# homeboard8.net
KiCad netlist of a schematic drawn in EAGLE
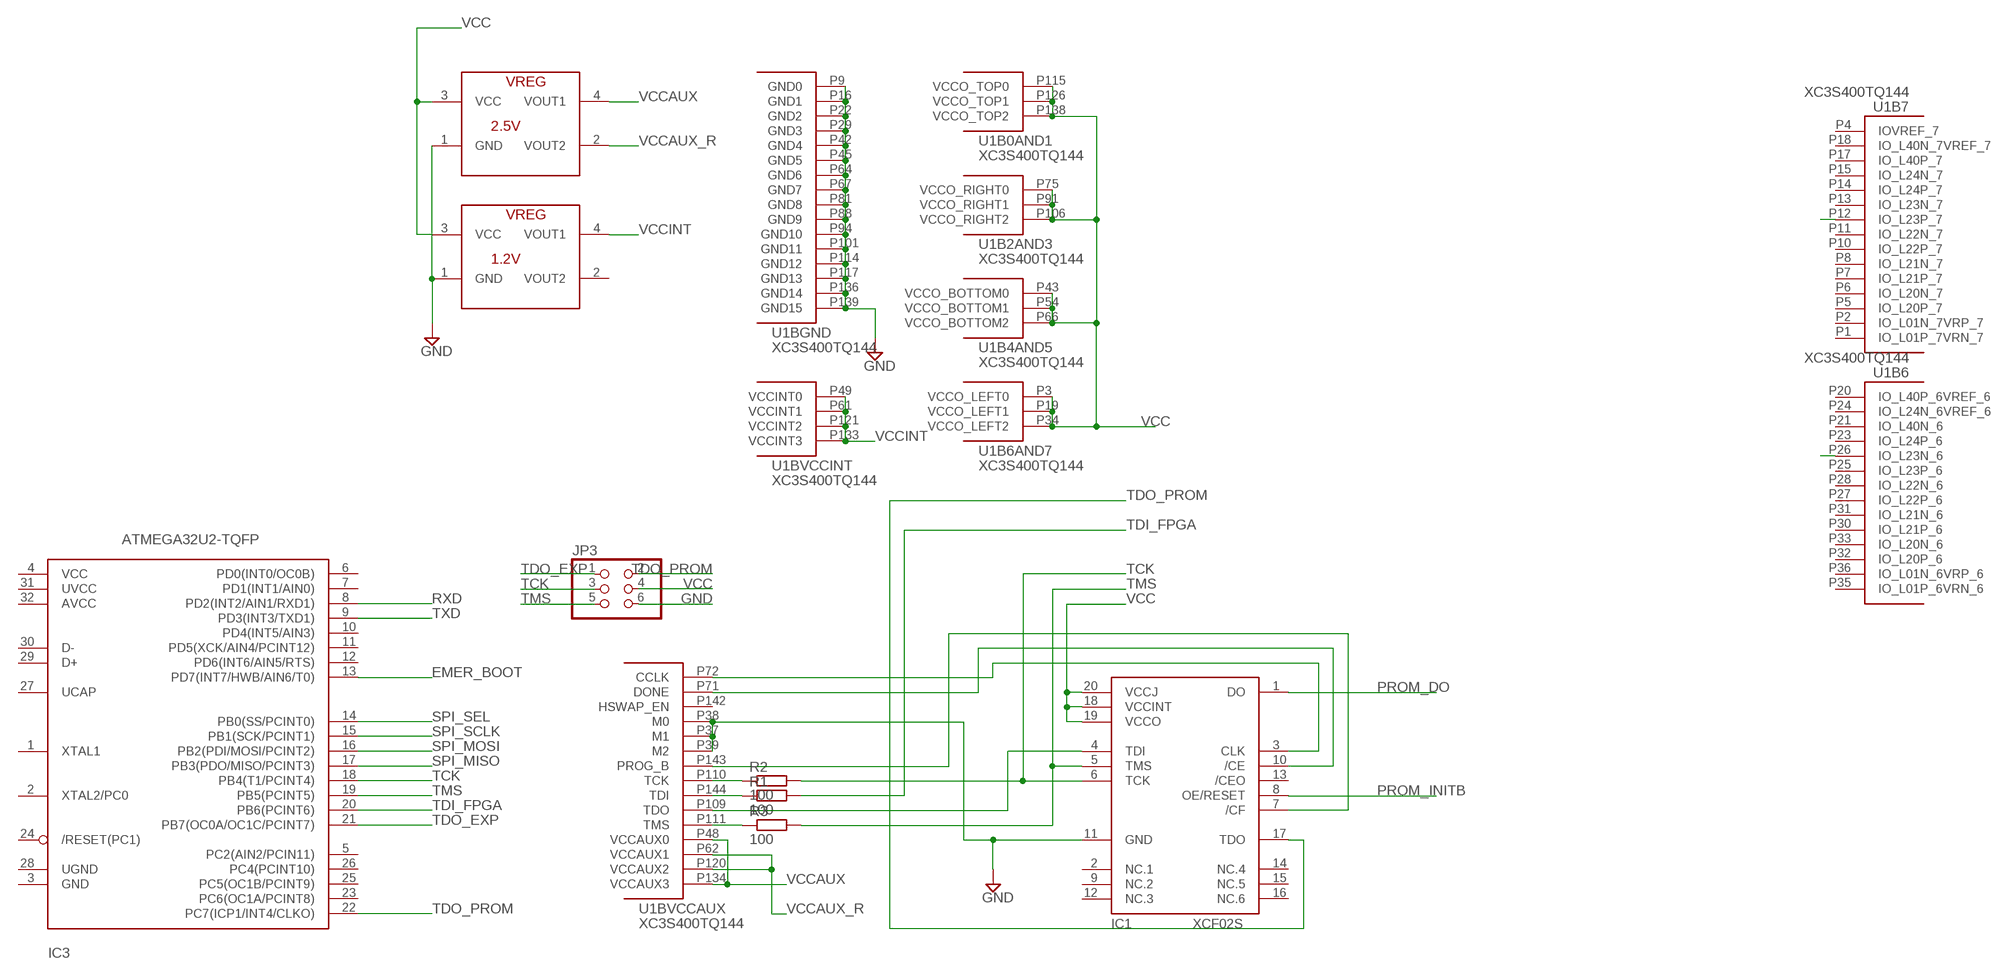
[diagram p0: schematic, sheet 1, part 1 of 3]
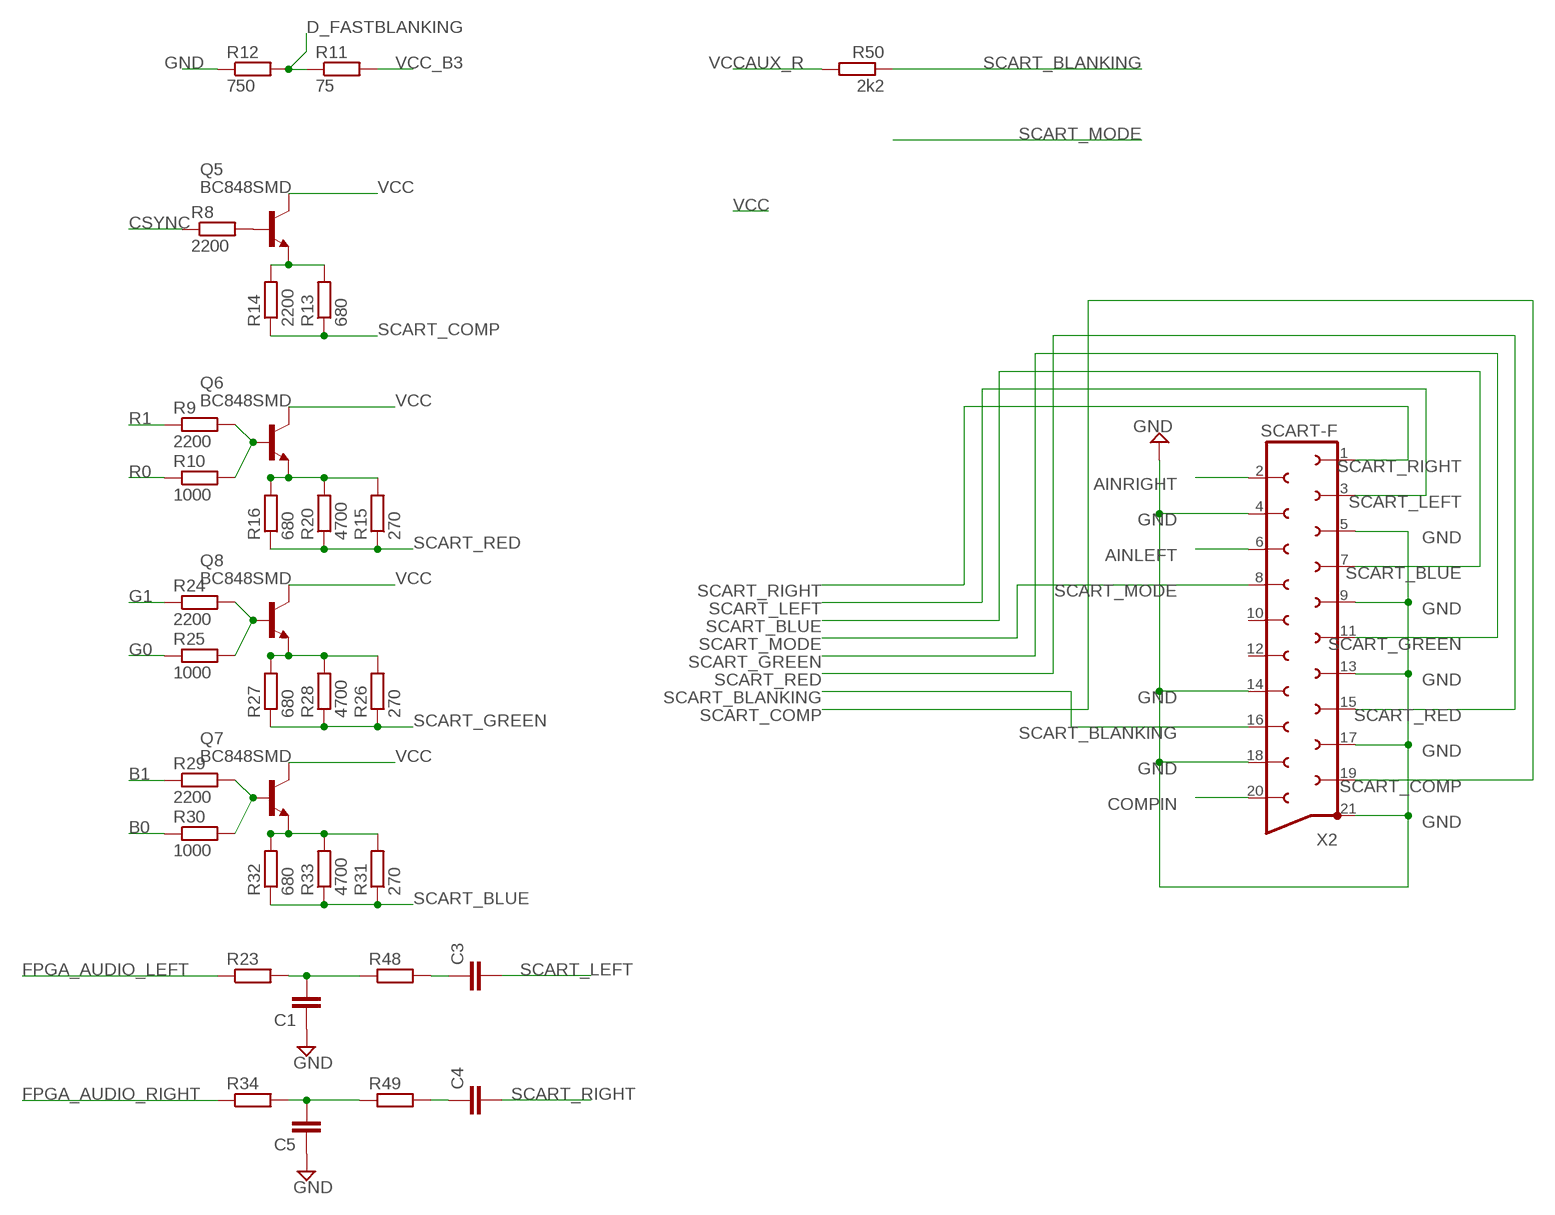
[diagram p1: schematic, sheet 1, part 2 of 3]
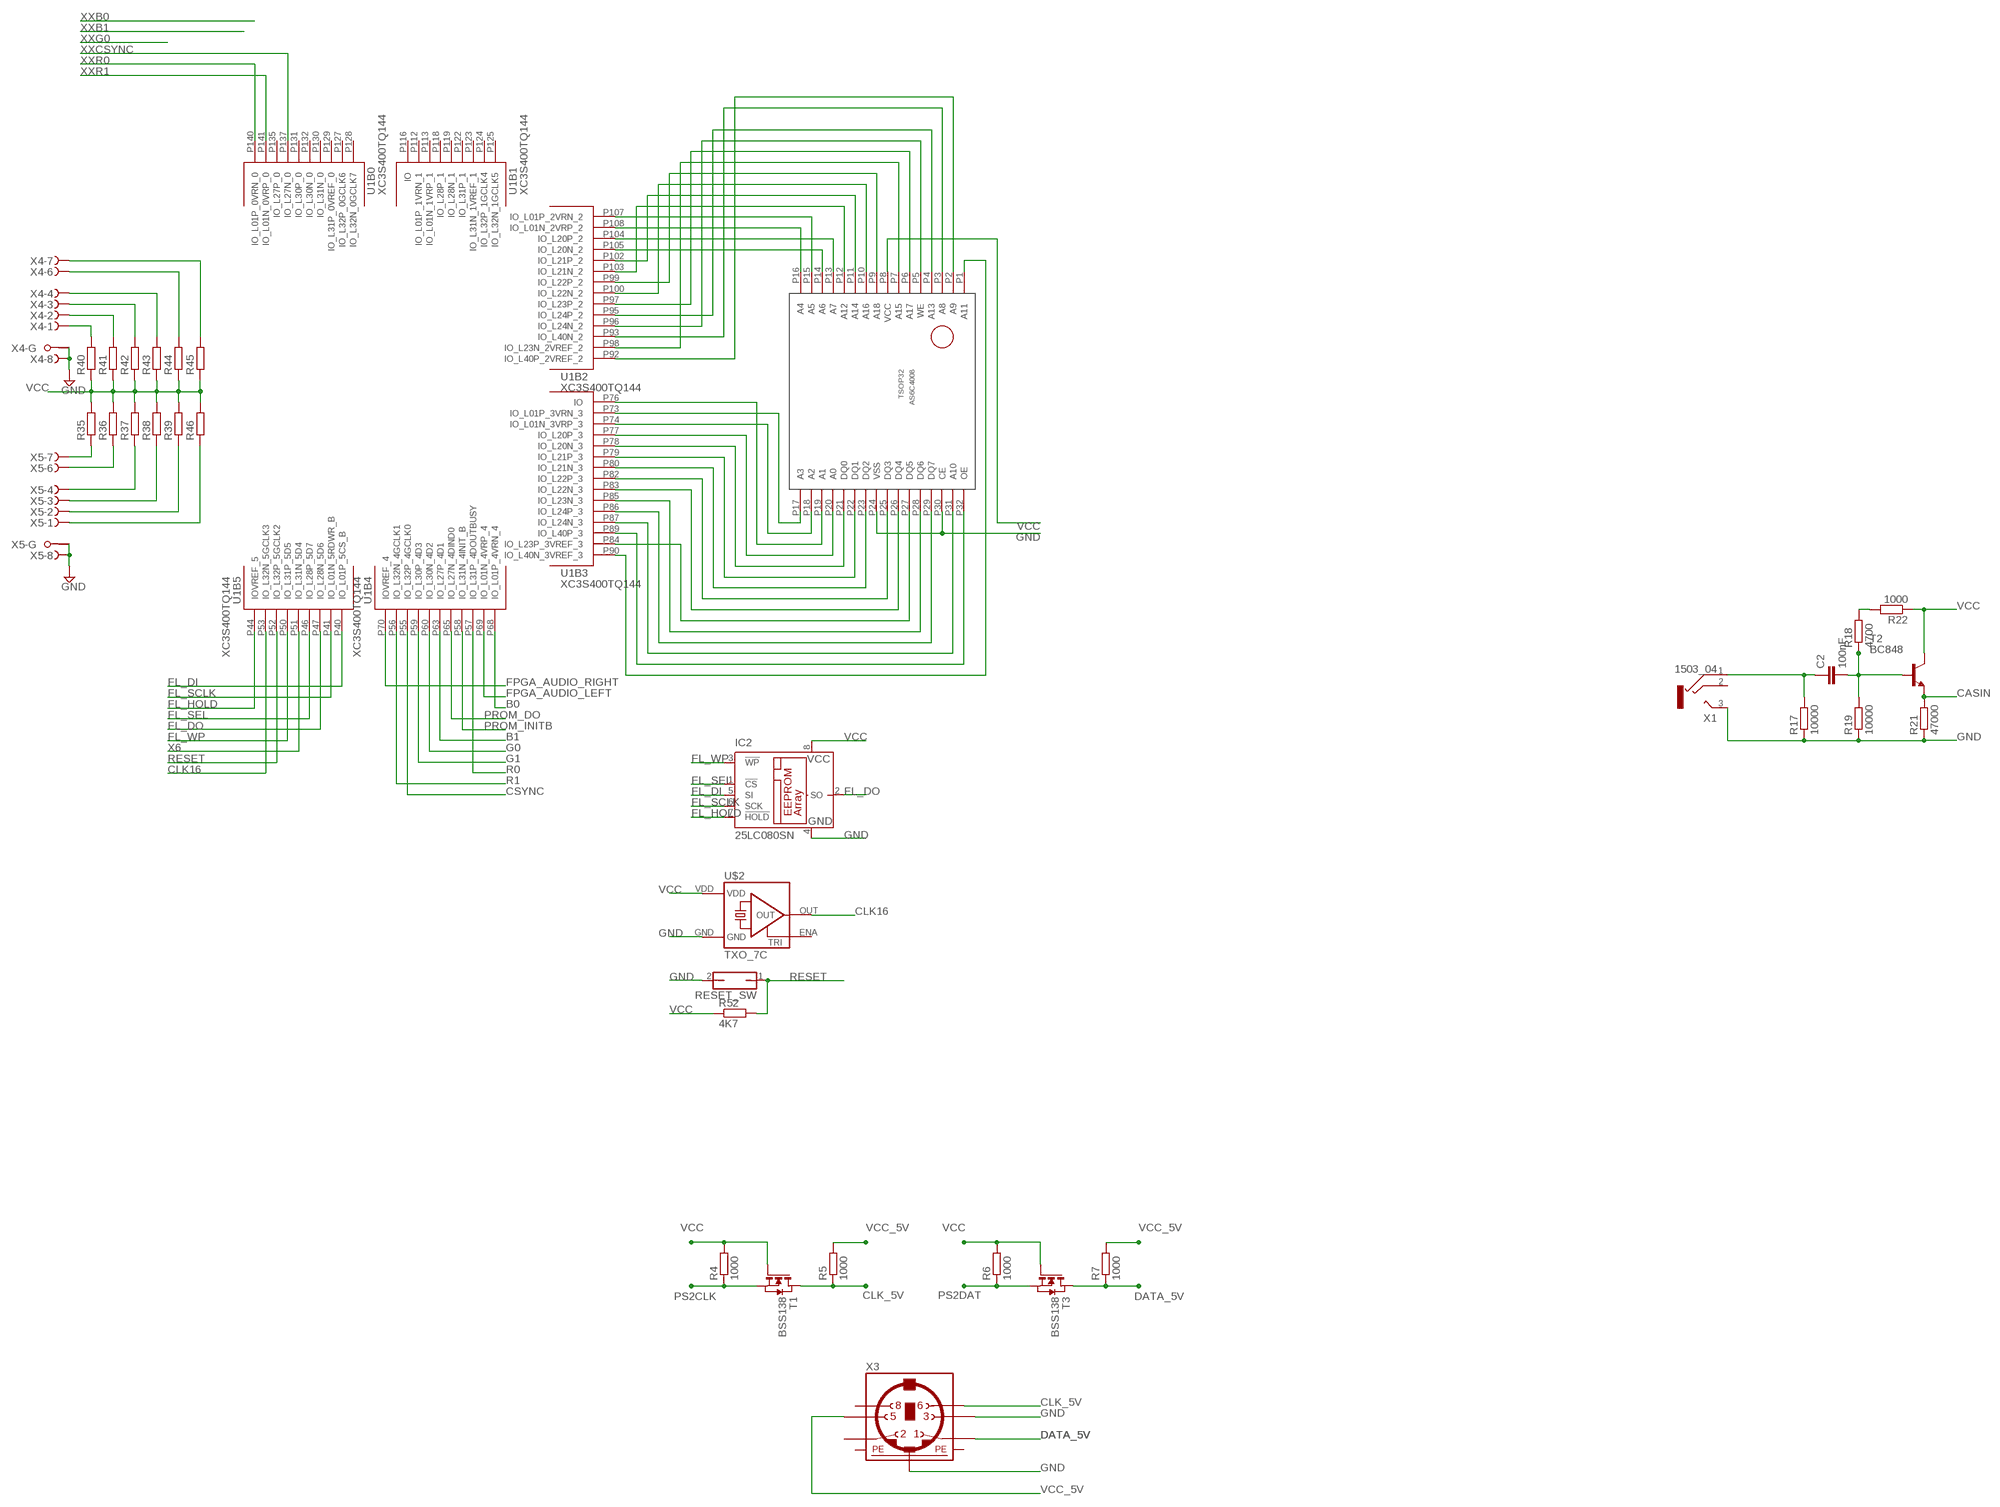
[diagram p2: schematic, sheet 1, part 3 of 3]

(export (version "E")
  (design (tool "Eeschema 10.0.6"))
  (components
    (comp (ref "C1")
      (value "C-EUC0603")
      (footprint "eagle-import:C0603")
      (libsource (lib "eagle-import") (part "C-EUC0603"))
    )
    (comp (ref "C2")
      (value "100nF")
      (footprint "eagle-import:C0603")
      (libsource (lib "eagle-import") (part "C-EUC0603"))
    )
    (comp (ref "C3")
      (value "C-EUC0603")
      (footprint "eagle-import:C0603")
      (libsource (lib "eagle-import") (part "C-EUC0603"))
    )
    (comp (ref "C4")
      (value "C-EUC0603")
      (footprint "eagle-import:C0603")
      (libsource (lib "eagle-import") (part "C-EUC0603"))
    )
    (comp (ref "C5")
      (value "C-EUC0603")
      (footprint "eagle-import:C0603")
      (libsource (lib "eagle-import") (part "C-EUC0603"))
    )
    (comp (ref "IC1")
      (value "XCF02S")
      (footprint "eagle-import:VO20")
      (libsource (lib "eagle-import") (part "XCF02S"))
    )
    (comp (ref "IC2")
      (value "25LC080SN")
      (footprint "eagle-import:SO-08")
      (fields (field (name "MF") "MICROCHIP") (field (name "MPN") "25LC080/SN"))
      (libsource (lib "eagle-import") (part "25SNLC080"))
    )
    (comp (ref "IC3")
      (value "ATMEGA32U2-TQFP")
      (footprint "eagle-import:TQFP32-08")
      (libsource (lib "eagle-import") (part "ATMEGA32U2-TQFP"))
    )
    (comp (ref "JP3")
      (value "PINHD-2X3")
      (footprint "eagle-import:2X03")
      (libsource (lib "eagle-import") (part "PINHD-2X3"))
    )
    (comp (ref "Q5")
      (value "BC848SMD")
      (footprint "eagle-import:SOT23")
      (libsource (lib "eagle-import") (part "BC848SMD"))
    )
    (comp (ref "Q6")
      (value "BC848SMD")
      (footprint "eagle-import:SOT23")
      (libsource (lib "eagle-import") (part "BC848SMD"))
    )
    (comp (ref "Q7")
      (value "BC848SMD")
      (footprint "eagle-import:SOT23")
      (libsource (lib "eagle-import") (part "BC848SMD"))
    )
    (comp (ref "Q8")
      (value "BC848SMD")
      (footprint "eagle-import:SOT23")
      (libsource (lib "eagle-import") (part "BC848SMD"))
    )
    (comp (ref "R1")
      (value "100")
      (footprint "eagle-import:R0805")
      (libsource (lib "eagle-import") (part "R-EU_R0805"))
    )
    (comp (ref "R2")
      (value "100")
      (footprint "eagle-import:R0805")
      (libsource (lib "eagle-import") (part "R-EU_R0805"))
    )
    (comp (ref "R3")
      (value "100")
      (footprint "eagle-import:R0805")
      (libsource (lib "eagle-import") (part "R-EU_R0805"))
    )
    (comp (ref "R4")
      (value "1000")
      (footprint "eagle-import:R0805")
      (libsource (lib "eagle-import") (part "R-EU_R0805"))
    )
    (comp (ref "R5")
      (value "1000")
      (footprint "eagle-import:R0805")
      (libsource (lib "eagle-import") (part "R-EU_R0805"))
    )
    (comp (ref "R6")
      (value "1000")
      (footprint "eagle-import:R0805")
      (libsource (lib "eagle-import") (part "R-EU_R0805"))
    )
    (comp (ref "R7")
      (value "1000")
      (footprint "eagle-import:R0805")
      (libsource (lib "eagle-import") (part "R-EU_R0805"))
    )
    (comp (ref "R8")
      (value "2200")
      (footprint "eagle-import:R0805")
      (libsource (lib "eagle-import") (part "R-EU_R0805"))
    )
    (comp (ref "R9")
      (value "2200")
      (footprint "eagle-import:R0805")
      (libsource (lib "eagle-import") (part "R-EU_R0805"))
    )
    (comp (ref "R10")
      (value "1000")
      (footprint "eagle-import:R0805")
      (libsource (lib "eagle-import") (part "R-EU_R0805"))
    )
    (comp (ref "R11")
      (value "75")
      (footprint "eagle-import:R0805")
      (libsource (lib "eagle-import") (part "R-EU_R0805"))
    )
    (comp (ref "R12")
      (value "750")
      (footprint "eagle-import:R0805")
      (libsource (lib "eagle-import") (part "R-EU_R0805"))
    )
    (comp (ref "R13")
      (value "680")
      (footprint "eagle-import:R0805")
      (libsource (lib "eagle-import") (part "R-EU_R0805"))
    )
    (comp (ref "R14")
      (value "2200")
      (footprint "eagle-import:R0805")
      (libsource (lib "eagle-import") (part "R-EU_R0805"))
    )
    (comp (ref "R15")
      (value "270")
      (footprint "eagle-import:R0805")
      (libsource (lib "eagle-import") (part "R-EU_R0805"))
    )
    (comp (ref "R16")
      (value "680")
      (footprint "eagle-import:R0805")
      (libsource (lib "eagle-import") (part "R-EU_R0805"))
    )
    (comp (ref "R17")
      (value "10000")
      (footprint "eagle-import:R0805")
      (libsource (lib "eagle-import") (part "R-EU_R0805"))
    )
    (comp (ref "R18")
      (value "4700")
      (footprint "eagle-import:R0805")
      (libsource (lib "eagle-import") (part "R-EU_R0805"))
    )
    (comp (ref "R19")
      (value "10000")
      (footprint "eagle-import:R0805")
      (libsource (lib "eagle-import") (part "R-EU_R0805"))
    )
    (comp (ref "R20")
      (value "4700")
      (footprint "eagle-import:R0805")
      (libsource (lib "eagle-import") (part "R-EU_R0805"))
    )
    (comp (ref "R21")
      (value "47000")
      (footprint "eagle-import:R0805")
      (libsource (lib "eagle-import") (part "R-EU_R0805"))
    )
    (comp (ref "R22")
      (value "1000")
      (footprint "eagle-import:R0805")
      (libsource (lib "eagle-import") (part "R-EU_R0805"))
    )
    (comp (ref "R23")
      (value "R-EU_M0805")
      (footprint "eagle-import:M0805")
      (libsource (lib "eagle-import") (part "resistor_R-EU_M0805"))
    )
    (comp (ref "R24")
      (value "2200")
      (footprint "eagle-import:R0805")
      (libsource (lib "eagle-import") (part "R-EU_R0805"))
    )
    (comp (ref "R25")
      (value "1000")
      (footprint "eagle-import:R0805")
      (libsource (lib "eagle-import") (part "R-EU_R0805"))
    )
    (comp (ref "R26")
      (value "270")
      (footprint "eagle-import:R0805")
      (libsource (lib "eagle-import") (part "R-EU_R0805"))
    )
    (comp (ref "R27")
      (value "680")
      (footprint "eagle-import:R0805")
      (libsource (lib "eagle-import") (part "R-EU_R0805"))
    )
    (comp (ref "R28")
      (value "4700")
      (footprint "eagle-import:R0805")
      (libsource (lib "eagle-import") (part "R-EU_R0805"))
    )
    (comp (ref "R29")
      (value "2200")
      (footprint "eagle-import:R0805")
      (libsource (lib "eagle-import") (part "R-EU_R0805"))
    )
    (comp (ref "R30")
      (value "1000")
      (footprint "eagle-import:R0805")
      (libsource (lib "eagle-import") (part "R-EU_R0805"))
    )
    (comp (ref "R31")
      (value "270")
      (footprint "eagle-import:R0805")
      (libsource (lib "eagle-import") (part "R-EU_R0805"))
    )
    (comp (ref "R32")
      (value "680")
      (footprint "eagle-import:R0805")
      (libsource (lib "eagle-import") (part "R-EU_R0805"))
    )
    (comp (ref "R33")
      (value "4700")
      (footprint "eagle-import:R0805")
      (libsource (lib "eagle-import") (part "R-EU_R0805"))
    )
    (comp (ref "R34")
      (value "R-EU_M0805")
      (footprint "eagle-import:M0805")
      (libsource (lib "eagle-import") (part "resistor_R-EU_M0805"))
    )
    (comp (ref "R35")
      (value "R-EU_M0805")
      (footprint "eagle-import:M0805")
      (libsource (lib "eagle-import") (part "resistor_R-EU_M0805"))
    )
    (comp (ref "R36")
      (value "R-EU_M0805")
      (footprint "eagle-import:M0805")
      (libsource (lib "eagle-import") (part "resistor_R-EU_M0805"))
    )
    (comp (ref "R37")
      (value "R-EU_M0805")
      (footprint "eagle-import:M0805")
      (libsource (lib "eagle-import") (part "resistor_R-EU_M0805"))
    )
    (comp (ref "R38")
      (value "R-EU_M0805")
      (footprint "eagle-import:M0805")
      (libsource (lib "eagle-import") (part "resistor_R-EU_M0805"))
    )
    (comp (ref "R39")
      (value "R-EU_M0805")
      (footprint "eagle-import:M0805")
      (libsource (lib "eagle-import") (part "resistor_R-EU_M0805"))
    )
    (comp (ref "R40")
      (value "R-EU_M0805")
      (footprint "eagle-import:M0805")
      (libsource (lib "eagle-import") (part "resistor_R-EU_M0805"))
    )
    (comp (ref "R41")
      (value "R-EU_M0805")
      (footprint "eagle-import:M0805")
      (libsource (lib "eagle-import") (part "resistor_R-EU_M0805"))
    )
    (comp (ref "R42")
      (value "R-EU_M0805")
      (footprint "eagle-import:M0805")
      (libsource (lib "eagle-import") (part "resistor_R-EU_M0805"))
    )
    (comp (ref "R43")
      (value "R-EU_M0805")
      (footprint "eagle-import:M0805")
      (libsource (lib "eagle-import") (part "resistor_R-EU_M0805"))
    )
    (comp (ref "R44")
      (value "R-EU_M0805")
      (footprint "eagle-import:M0805")
      (libsource (lib "eagle-import") (part "resistor_R-EU_M0805"))
    )
    (comp (ref "R45")
      (value "R-EU_M0805")
      (footprint "eagle-import:M0805")
      (libsource (lib "eagle-import") (part "resistor_R-EU_M0805"))
    )
    (comp (ref "R46")
      (value "R-EU_M0805")
      (footprint "eagle-import:M0805")
      (libsource (lib "eagle-import") (part "resistor_R-EU_M0805"))
    )
    (comp (ref "R48")
      (value "R-EU_M0805")
      (footprint "eagle-import:M0805")
      (libsource (lib "eagle-import") (part "resistor_R-EU_M0805"))
    )
    (comp (ref "R49")
      (value "R-EU_M0805")
      (footprint "eagle-import:M0805")
      (libsource (lib "eagle-import") (part "resistor_R-EU_M0805"))
    )
    (comp (ref "R50")
      (value "2k2")
      (footprint "eagle-import:M0805")
      (libsource (lib "eagle-import") (part "resistor_R-EU_M0805"))
    )
    (comp (ref "R52")
      (value "4K7")
      (footprint "eagle-import:M0805")
      (libsource (lib "eagle-import") (part "resistor_R-EU_M0805"))
    )
    (comp (ref "REG1.2")
      (value "1.2V")
      (footprint "eagle-import:SOT223")
      (libsource (lib "eagle-import") (part "NX1117"))
    )
    (comp (ref "REG2.5")
      (value "2.5V")
      (footprint "eagle-import:SOT223")
      (libsource (lib "eagle-import") (part "NX1117"))
    )
    (comp (ref "RESET_SW")
      (value "JP1Q")
      (footprint "eagle-import:JP1")
      (libsource (lib "eagle-import") (part "JP1Q"))
    )
    (comp (ref "T1")
      (value "BSS138")
      (footprint "eagle-import:SOT-23")
      (libsource (lib "eagle-import") (part "NMOSSOT23"))
    )
    (comp (ref "T2")
      (value "BC848")
      (footprint "eagle-import:SOT23")
      (libsource (lib "eagle-import") (part "BC848"))
    )
    (comp (ref "T3")
      (value "BSS138")
      (footprint "eagle-import:SOT-23")
      (libsource (lib "eagle-import") (part "NMOSSOT23"))
    )
    (comp (ref "U$1")
      (value "AS6C4008")
      (footprint "eagle-import:TSOP32")
      (libsource (lib "eagle-import") (part "AS6C4008"))
    )
    (comp (ref "U$2")
      (value "TXO_7C")
      (footprint "eagle-import:OSC_7C")
      (libsource (lib "eagle-import") (part "TXO_7C"))
    )
    (comp (ref "U1")
      (value "XC3S400TQ144")
      (footprint "eagle-import:TQ144")
      (libsource (lib "eagle-import") (part "XC3S400TQ144"))
    )
    (comp (ref "X1")
      (value "1503_04")
      (footprint "eagle-import:1503_04")
      (libsource (lib "eagle-import") (part "1503_04"))
    )
    (comp (ref "X2")
      (value "SCART-F")
      (footprint "eagle-import:SCART-F")
      (libsource (lib "eagle-import") (part "SCART-F"))
    )
    (comp (ref "X3")
      (value "MINI_DIN_6")
      (footprint "eagle-import:M_DIN6")
      (libsource (lib "eagle-import") (part "MINI_DIN_6"))
    )
    (comp (ref "X4")
      (value "F09HPS")
      (footprint "eagle-import:F09HP")
      (libsource (lib "eagle-import") (part "F09HPS"))
    )
    (comp (ref "X5")
      (value "F09HPS")
      (footprint "eagle-import:F09HP")
      (libsource (lib "eagle-import") (part "F09HPS"))
    )
  )
  (nets
    (net (code "1") (name "/AINLEFT") (class "Default")
      (node (ref "X2") (pin "6") (pinfunction "6_6") (pintype "passive"))
    )
    (net (code "2") (name "/AINRIGHT") (class "Default")
      (node (ref "X2") (pin "2") (pinfunction "2_2") (pintype "passive"))
    )
    (net (code "3") (name "/B0") (class "Default")
      (node (ref "R30") (pin "1") (pinfunction "1_1") (pintype "passive"))
      (node (ref "U1") (pin "P68") (pinfunction "IO_L01P_4VRN_4_P68") (pintype "bidirectional"))
    )
    (net (code "4") (name "/B1") (class "Default")
      (node (ref "R29") (pin "1") (pinfunction "1_1") (pintype "passive"))
      (node (ref "U1") (pin "P63") (pinfunction "IO_L27P_4D1_P63") (pintype "bidirectional"))
    )
    (net (code "5") (name "/CASIN") (class "Default")
      (node (ref "R21") (pin "2") (pinfunction "2_2") (pintype "passive"))
      (node (ref "T2") (pin "2") (pinfunction "E_2") (pintype "passive"))
    )
    (net (code "6") (name "/CLK16") (class "Default")
      (node (ref "U$2") (pin "OUT") (pinfunction "OUT_OUT") (pintype "output"))
      (node (ref "U1") (pin "P53") (pinfunction "IO_L32N_5GCLK3_P53") (pintype "bidirectional"))
    )
    (net (code "7") (name "/CLK_5V") (class "Default")
      (node (ref "R5") (pin "1") (pinfunction "1_1") (pintype "passive"))
      (node (ref "T1") (pin "1") (pinfunction "D_1") (pintype "passive"))
      (node (ref "X3") (pin "6") (pinfunction "6_6") (pintype "passive"))
    )
    (net (code "8") (name "/COMPIN") (class "Default")
      (node (ref "X2") (pin "20") (pinfunction "20_20") (pintype "passive"))
    )
    (net (code "9") (name "/CSYNC") (class "Default")
      (node (ref "R8") (pin "1") (pinfunction "1_1") (pintype "passive"))
      (node (ref "U1") (pin "P55") (pinfunction "IO_L32P_4GCLK0_P55") (pintype "bidirectional"))
    )
    (net (code "10") (name "/DATA_5V") (class "Default")
      (node (ref "R7") (pin "1") (pinfunction "1_1") (pintype "passive"))
      (node (ref "T3") (pin "1") (pinfunction "D_1") (pintype "passive"))
      (node (ref "X3") (pin "1") (pinfunction "1_1") (pintype "passive"))
    )
    (net (code "11") (name "/D_FASTBLANKING") (class "Default")
      (node (ref "R11") (pin "1") (pinfunction "1_1") (pintype "passive"))
      (node (ref "R12") (pin "2") (pinfunction "2_2") (pintype "passive"))
    )
    (net (code "12") (name "/EMER_BOOT") (class "Default")
      (node (ref "IC3") (pin "13") (pinfunction "PD7(INT7/HWB/AIN6/T0)_13") (pintype "bidirectional"))
    )
    (net (code "13") (name "/FL_DI") (class "Default")
      (node (ref "IC2") (pin "5") (pinfunction "SI_5") (pintype "input"))
      (node (ref "U1") (pin "P40") (pinfunction "IO_L01P_5CS_B_P40") (pintype "bidirectional"))
    )
    (net (code "14") (name "/FL_DO") (class "Default")
      (node (ref "IC2") (pin "2") (pinfunction "SO_2") (pintype "bidirectional"))
      (node (ref "U1") (pin "P47") (pinfunction "IO_L28N_5D6_P47") (pintype "bidirectional"))
    )
    (net (code "15") (name "/FL_HOLD") (class "Default")
      (node (ref "IC2") (pin "7") (pinfunction "~{HOLD}_7") (pintype "input"))
      (node (ref "U1") (pin "P44") (pinfunction "IOVREF_5_P44") (pintype "bidirectional"))
    )
    (net (code "16") (name "/FL_SCLK") (class "Default")
      (node (ref "IC2") (pin "6") (pinfunction "SCK_6") (pintype "input"))
      (node (ref "U1") (pin "P41") (pinfunction "IO_L01N_5RDWR_B_P41") (pintype "bidirectional"))
    )
    (net (code "17") (name "/FL_SEL") (class "Default")
      (node (ref "IC2") (pin "1") (pinfunction "~{CS}_1") (pintype "input"))
      (node (ref "U1") (pin "P46") (pinfunction "IO_L28P_5D7_P46") (pintype "bidirectional"))
    )
    (net (code "18") (name "/FL_WP") (class "Default")
      (node (ref "IC2") (pin "3") (pinfunction "~{WP}_3") (pintype "input"))
      (node (ref "U1") (pin "P50") (pinfunction "IO_L31P_5D5_P50") (pintype "bidirectional"))
    )
    (net (code "19") (name "/FPGA_AUDIO_LEFT") (class "Default")
      (node (ref "R23") (pin "1") (pinfunction "1_1") (pintype "passive"))
      (node (ref "U1") (pin "P69") (pinfunction "IO_L01N_4VRP_4_P69") (pintype "bidirectional"))
    )
    (net (code "20") (name "/FPGA_AUDIO_RIGHT") (class "Default")
      (node (ref "R34") (pin "1") (pinfunction "1_1") (pintype "passive"))
      (node (ref "U1") (pin "P70") (pinfunction "IOVREF_4_P70") (pintype "bidirectional"))
    )
    (net (code "21") (name "/G0") (class "Default")
      (node (ref "R25") (pin "1") (pinfunction "1_1") (pintype "passive"))
      (node (ref "U1") (pin "P60") (pinfunction "IO_L30N_4D2_P60") (pintype "bidirectional"))
    )
    (net (code "22") (name "/G1") (class "Default")
      (node (ref "R24") (pin "1") (pinfunction "1_1") (pintype "passive"))
      (node (ref "U1") (pin "P59") (pinfunction "IO_L30P_4D3_P59") (pintype "bidirectional"))
    )
    (net (code "23") (name "/PE1") (class "Default")
      (node (ref "X3") (pin "SH1") (pinfunction "PE1_SH1") (pintype "power_in"))
    )
    (net (code "24") (name "/PE3") (class "Default")
      (node (ref "X3") (pin "SH3") (pinfunction "PE3_SH3") (pintype "power_in"))
    )
    (net (code "25") (name "/PROM_DO") (class "Default")
      (node (ref "IC1") (pin "1") (pinfunction "DO_1") (pintype "bidirectional"))
      (node (ref "U1") (pin "P65") (pinfunction "IO_L27N_4DIND0_P65") (pintype "bidirectional"))
    )
    (net (code "26") (name "/PROM_INITB") (class "Default")
      (node (ref "IC1") (pin "8") (pinfunction "OE/RESET_8") (pintype "bidirectional"))
      (node (ref "U1") (pin "P58") (pinfunction "IO_L31N_4INIT_B_P58") (pintype "bidirectional"))
    )
    (net (code "27") (name "/PS2CLK") (class "Default")
      (node (ref "R4") (pin "1") (pinfunction "1_1") (pintype "passive"))
      (node (ref "T1") (pin "2") (pinfunction "S_2") (pintype "passive"))
    )
    (net (code "28") (name "/PS2DAT") (class "Default")
      (node (ref "R6") (pin "1") (pinfunction "1_1") (pintype "passive"))
      (node (ref "T3") (pin "2") (pinfunction "S_2") (pintype "passive"))
    )
    (net (code "29") (name "/R0") (class "Default")
      (node (ref "R10") (pin "1") (pinfunction "1_1") (pintype "passive"))
      (node (ref "U1") (pin "P57") (pinfunction "IO_L31P_4DOUTBUSY_P57") (pintype "bidirectional"))
    )
    (net (code "30") (name "/R1") (class "Default")
      (node (ref "R9") (pin "1") (pinfunction "1_1") (pintype "passive"))
      (node (ref "U1") (pin "P56") (pinfunction "IO_L32N_4GCLK1_P56") (pintype "bidirectional"))
    )
    (net (code "31") (name "/RESET") (class "Default")
      (node (ref "R52") (pin "2") (pinfunction "2_2") (pintype "passive"))
      (node (ref "RESET_SW") (pin "1") (pinfunction "1_1") (pintype "passive"))
      (node (ref "U1") (pin "P52") (pinfunction "IO_L32P_5GCLK2_P52") (pintype "bidirectional"))
    )
    (net (code "32") (name "/RXD") (class "Default")
      (node (ref "IC3") (pin "8") (pinfunction "PD2(INT2/AIN1/RXD1)_8") (pintype "bidirectional"))
    )
    (net (code "33") (name "/SCART_BLANKING") (class "Default")
      (node (ref "R50") (pin "1") (pinfunction "1_1") (pintype "passive"))
      (node (ref "X2") (pin "16") (pinfunction "16_16") (pintype "passive"))
    )
    (net (code "34") (name "/SCART_BLUE") (class "Default")
      (node (ref "R31") (pin "1") (pinfunction "1_1") (pintype "passive"))
      (node (ref "R32") (pin "1") (pinfunction "1_1") (pintype "passive"))
      (node (ref "R33") (pin "1") (pinfunction "1_1") (pintype "passive"))
      (node (ref "X2") (pin "7") (pinfunction "7_7") (pintype "passive"))
    )
    (net (code "35") (name "/SCART_COMP") (class "Default")
      (node (ref "R13") (pin "1") (pinfunction "1_1") (pintype "passive"))
      (node (ref "R14") (pin "1") (pinfunction "1_1") (pintype "passive"))
      (node (ref "X2") (pin "19") (pinfunction "19_19") (pintype "passive"))
    )
    (net (code "36") (name "/SCART_GREEN") (class "Default")
      (node (ref "R26") (pin "1") (pinfunction "1_1") (pintype "passive"))
      (node (ref "R27") (pin "1") (pinfunction "1_1") (pintype "passive"))
      (node (ref "R28") (pin "1") (pinfunction "1_1") (pintype "passive"))
      (node (ref "X2") (pin "11") (pinfunction "11_11") (pintype "passive"))
    )
    (net (code "37") (name "/SCART_LEFT") (class "Default")
      (node (ref "C3") (pin "2") (pinfunction "2_2") (pintype "passive"))
      (node (ref "X2") (pin "3") (pinfunction "3_3") (pintype "passive"))
    )
    (net (code "38") (name "/SCART_MODE") (class "Default")
      (node (ref "X2") (pin "8") (pinfunction "8_8") (pintype "passive"))
    )
    (net (code "39") (name "/SCART_RED") (class "Default")
      (node (ref "R15") (pin "1") (pinfunction "1_1") (pintype "passive"))
      (node (ref "R16") (pin "1") (pinfunction "1_1") (pintype "passive"))
      (node (ref "R20") (pin "1") (pinfunction "1_1") (pintype "passive"))
      (node (ref "X2") (pin "15") (pinfunction "15_15") (pintype "passive"))
    )
    (net (code "40") (name "/SCART_RIGHT") (class "Default")
      (node (ref "C4") (pin "2") (pinfunction "2_2") (pintype "passive"))
      (node (ref "X2") (pin "1") (pinfunction "1_1") (pintype "passive"))
    )
    (net (code "41") (name "/SPI_MISO") (class "Default")
      (node (ref "IC3") (pin "17") (pinfunction "PB3(PDO/MISO/PCINT3)_17") (pintype "bidirectional"))
    )
    (net (code "42") (name "/SPI_MOSI") (class "Default")
      (node (ref "IC3") (pin "16") (pinfunction "PB2(PDI/MOSI/PCINT2)_16") (pintype "bidirectional"))
    )
    (net (code "43") (name "/SPI_SCLK") (class "Default")
      (node (ref "IC3") (pin "15") (pinfunction "PB1(SCK/PCINT1)_15") (pintype "bidirectional"))
    )
    (net (code "44") (name "/SPI_SEL") (class "Default")
      (node (ref "IC3") (pin "14") (pinfunction "PB0(SS/PCINT0)_14") (pintype "bidirectional"))
    )
    (net (code "45") (name "/TCK") (class "Default")
      (node (ref "IC1") (pin "6") (pinfunction "TCK_6") (pintype "bidirectional"))
      (node (ref "IC3") (pin "18") (pinfunction "PB4(T1/PCINT4)_18") (pintype "bidirectional"))
      (node (ref "JP3") (pin "3") (pinfunction "3_3") (pintype "passive"))
      (node (ref "R2") (pin "2") (pinfunction "2_2") (pintype "passive"))
    )
    (net (code "46") (name "/TDI_FPGA") (class "Default")
      (node (ref "IC3") (pin "20") (pinfunction "PB6(PCINT6)_20") (pintype "bidirectional"))
      (node (ref "R1") (pin "2") (pinfunction "2_2") (pintype "passive"))
    )
    (net (code "47") (name "/TDO_EXP") (class "Default")
      (node (ref "IC3") (pin "21") (pinfunction "PB7(OC0A/OC1C/PCINT7)_21") (pintype "bidirectional"))
      (node (ref "JP3") (pin "1") (pinfunction "1_1") (pintype "passive"))
    )
    (net (code "48") (name "/TDO_PROM") (class "Default")
      (node (ref "IC1") (pin "17") (pinfunction "TDO_17") (pintype "bidirectional"))
      (node (ref "IC3") (pin "22") (pinfunction "PC7(ICP1/INT4/CLKO)_22") (pintype "bidirectional"))
      (node (ref "JP3") (pin "2") (pinfunction "2_2") (pintype "passive"))
    )
    (net (code "49") (name "/TMS") (class "Default")
      (node (ref "IC1") (pin "5") (pinfunction "TMS_5") (pintype "bidirectional"))
      (node (ref "IC3") (pin "19") (pinfunction "PB5(PCINT5)_19") (pintype "bidirectional"))
      (node (ref "JP3") (pin "5") (pinfunction "5_5") (pintype "passive"))
      (node (ref "R3") (pin "2") (pinfunction "2_2") (pintype "passive"))
    )
    (net (code "50") (name "/TXD") (class "Default")
      (node (ref "IC3") (pin "9") (pinfunction "PD3(INT3/TXD1)_9") (pintype "bidirectional"))
    )
    (net (code "51") (name "/VCC") (class "Default")
      (node (ref "IC1") (pin "18") (pinfunction "VCCINT_18") (pintype "bidirectional"))
      (node (ref "IC1") (pin "19") (pinfunction "VCCO_19") (pintype "bidirectional"))
      (node (ref "IC1") (pin "20") (pinfunction "VCCJ_20") (pintype "bidirectional"))
      (node (ref "IC2") (pin "8") (pinfunction "VCC_8") (pintype "power_in"))
      (node (ref "JP3") (pin "4") (pinfunction "4_4") (pintype "passive"))
      (node (ref "Q5") (pin "3") (pinfunction "C_3") (pintype "passive"))
      (node (ref "Q6") (pin "3") (pinfunction "C_3") (pintype "passive"))
      (node (ref "Q7") (pin "3") (pinfunction "C_3") (pintype "passive"))
      (node (ref "Q8") (pin "3") (pinfunction "C_3") (pintype "passive"))
      (node (ref "R22") (pin "1") (pinfunction "1_1") (pintype "passive"))
      (node (ref "R35") (pin "2") (pinfunction "2_2") (pintype "passive"))
      (node (ref "R36") (pin "2") (pinfunction "2_2") (pintype "passive"))
      (node (ref "R37") (pin "2") (pinfunction "2_2") (pintype "passive"))
      (node (ref "R38") (pin "2") (pinfunction "2_2") (pintype "passive"))
      (node (ref "R39") (pin "2") (pinfunction "2_2") (pintype "passive"))
      (node (ref "R4") (pin "2") (pinfunction "2_2") (pintype "passive"))
      (node (ref "R40") (pin "1") (pinfunction "1_1") (pintype "passive"))
      (node (ref "R41") (pin "1") (pinfunction "1_1") (pintype "passive"))
      (node (ref "R42") (pin "1") (pinfunction "1_1") (pintype "passive"))
      (node (ref "R43") (pin "1") (pinfunction "1_1") (pintype "passive"))
      (node (ref "R44") (pin "1") (pinfunction "1_1") (pintype "passive"))
      (node (ref "R45") (pin "1") (pinfunction "1_1") (pintype "passive"))
      (node (ref "R46") (pin "2") (pinfunction "2_2") (pintype "passive"))
      (node (ref "R52") (pin "1") (pinfunction "1_1") (pintype "passive"))
      (node (ref "R6") (pin "2") (pinfunction "2_2") (pintype "passive"))
      (node (ref "REG1.2") (pin "3") (pinfunction "VCC_3") (pintype "bidirectional"))
      (node (ref "REG2.5") (pin "3") (pinfunction "VCC_3") (pintype "bidirectional"))
      (node (ref "T1") (pin "3") (pinfunction "G_3") (pintype "passive"))
      (node (ref "T2") (pin "3") (pinfunction "C_3") (pintype "passive"))
      (node (ref "T3") (pin "3") (pinfunction "G_3") (pintype "passive"))
      (node (ref "U$1") (pin "P8") (pinfunction "VCC_P8") (pintype "bidirectional"))
      (node (ref "U$2") (pin "VDD") (pinfunction "VDD_VDD") (pintype "power_in"))
      (node (ref "U1") (pin "P106") (pinfunction "VCCO_RIGHT2_P106") (pintype "passive"))
      (node (ref "U1") (pin "P115") (pinfunction "VCCO_TOP0_P115") (pintype "passive"))
      (node (ref "U1") (pin "P126") (pinfunction "VCCO_TOP1_P126") (pintype "passive"))
      (node (ref "U1") (pin "P138") (pinfunction "VCCO_TOP2_P138") (pintype "passive"))
      (node (ref "U1") (pin "P19") (pinfunction "VCCO_LEFT1_P19") (pintype "passive"))
      (node (ref "U1") (pin "P3") (pinfunction "VCCO_LEFT0_P3") (pintype "passive"))
      (node (ref "U1") (pin "P34") (pinfunction "VCCO_LEFT2_P34") (pintype "passive"))
      (node (ref "U1") (pin "P43") (pinfunction "VCCO_BOTTOM0_P43") (pintype "passive"))
      (node (ref "U1") (pin "P54") (pinfunction "VCCO_BOTTOM1_P54") (pintype "passive"))
      (node (ref "U1") (pin "P66") (pinfunction "VCCO_BOTTOM2_P66") (pintype "passive"))
      (node (ref "U1") (pin "P75") (pinfunction "VCCO_RIGHT0_P75") (pintype "passive"))
      (node (ref "U1") (pin "P91") (pinfunction "VCCO_RIGHT1_P91") (pintype "passive"))
    )
    (net (code "52") (name "/VCCAUX") (class "Default")
      (node (ref "REG2.5") (pin "4") (pinfunction "VOUT1_4") (pintype "bidirectional"))
      (node (ref "U1") (pin "P134") (pinfunction "VCCAUX3_P134") (pintype "passive"))
      (node (ref "U1") (pin "P48") (pinfunction "VCCAUX0_P48") (pintype "passive"))
    )
    (net (code "53") (name "/VCCAUX_R") (class "Default")
      (node (ref "R50") (pin "2") (pinfunction "2_2") (pintype "passive"))
      (node (ref "REG2.5") (pin "2") (pinfunction "VOUT2_2") (pintype "bidirectional"))
      (node (ref "U1") (pin "P120") (pinfunction "VCCAUX2_P120") (pintype "passive"))
      (node (ref "U1") (pin "P62") (pinfunction "VCCAUX1_P62") (pintype "passive"))
    )
    (net (code "54") (name "/VCCINT") (class "Default")
      (node (ref "REG1.2") (pin "4") (pinfunction "VOUT1_4") (pintype "bidirectional"))
      (node (ref "U1") (pin "P121") (pinfunction "VCCINT2_P121") (pintype "passive"))
      (node (ref "U1") (pin "P133") (pinfunction "VCCINT3_P133") (pintype "passive"))
      (node (ref "U1") (pin "P49") (pinfunction "VCCINT0_P49") (pintype "passive"))
      (node (ref "U1") (pin "P61") (pinfunction "VCCINT1_P61") (pintype "passive"))
    )
    (net (code "55") (name "/VCC_5V") (class "Default")
      (node (ref "R5") (pin "2") (pinfunction "2_2") (pintype "passive"))
      (node (ref "R7") (pin "2") (pinfunction "2_2") (pintype "passive"))
      (node (ref "X3") (pin "5") (pinfunction "5_5") (pintype "passive"))
    )
    (net (code "56") (name "/VCC_B3") (class "Default")
      (node (ref "R11") (pin "2") (pinfunction "2_2") (pintype "passive"))
    )
    (net (code "57") (name "/X6") (class "Default")
      (node (ref "U1") (pin "P51") (pinfunction "IO_L31N_5D4_P51") (pintype "bidirectional"))
    )
    (net (code "60") (name "/XXCSYNC") (class "Default")
      (node (ref "U1") (pin "P137") (pinfunction "IO_L27N_0_P137") (pintype "bidirectional"))
    )
    (net (code "62") (name "/XXR0") (class "Default")
      (node (ref "U1") (pin "P140") (pinfunction "IO_L01P_0VRN_0_P140") (pintype "bidirectional"))
    )
    (net (code "63") (name "/XXR1") (class "Default")
      (node (ref "U1") (pin "P141") (pinfunction "IO_L01N_0VRP_0_P141") (pintype "bidirectional"))
    )
    (net (code "64") (name "GND") (class "Default")
      (node (ref "C1") (pin "1") (pinfunction "1_1") (pintype "passive"))
      (node (ref "C5") (pin "1") (pinfunction "1_1") (pintype "passive"))
      (node (ref "IC1") (pin "11") (pinfunction "GND_11") (pintype "bidirectional"))
      (node (ref "IC2") (pin "4") (pinfunction "GND_4") (pintype "power_in"))
      (node (ref "JP3") (pin "6") (pinfunction "6_6") (pintype "passive"))
      (node (ref "R12") (pin "1") (pinfunction "1_1") (pintype "passive"))
      (node (ref "R17") (pin "1") (pinfunction "1_1") (pintype "passive"))
      (node (ref "R19") (pin "1") (pinfunction "1_1") (pintype "passive"))
      (node (ref "R21") (pin "1") (pinfunction "1_1") (pintype "passive"))
      (node (ref "REG1.2") (pin "1") (pinfunction "GND_1") (pintype "bidirectional"))
      (node (ref "REG2.5") (pin "1") (pinfunction "GND_1") (pintype "bidirectional"))
      (node (ref "RESET_SW") (pin "2") (pinfunction "2_2") (pintype "passive"))
      (node (ref "U$1") (pin "P24") (pinfunction "VSS_P24") (pintype "bidirectional"))
      (node (ref "U$1") (pin "P30") (pinfunction "CE_P30") (pintype "bidirectional"))
      (node (ref "U$2") (pin "GND") (pinfunction "GND_GND") (pintype "power_in"))
      (node (ref "U1") (pin "P101") (pinfunction "GND11_P101") (pintype "passive"))
      (node (ref "U1") (pin "P114") (pinfunction "GND12_P114") (pintype "passive"))
      (node (ref "U1") (pin "P117") (pinfunction "GND13_P117") (pintype "passive"))
      (node (ref "U1") (pin "P136") (pinfunction "GND14_P136") (pintype "passive"))
      (node (ref "U1") (pin "P139") (pinfunction "GND15_P139") (pintype "passive"))
      (node (ref "U1") (pin "P16") (pinfunction "GND1_P16") (pintype "passive"))
      (node (ref "U1") (pin "P22") (pinfunction "GND2_P22") (pintype "passive"))
      (node (ref "U1") (pin "P29") (pinfunction "GND3_P29") (pintype "passive"))
      (node (ref "U1") (pin "P37") (pinfunction "M1_P37") (pintype "bidirectional"))
      (node (ref "U1") (pin "P38") (pinfunction "M0_P38") (pintype "bidirectional"))
      (node (ref "U1") (pin "P39") (pinfunction "M2_P39") (pintype "bidirectional"))
      (node (ref "U1") (pin "P42") (pinfunction "GND4_P42") (pintype "passive"))
      (node (ref "U1") (pin "P45") (pinfunction "GND5_P45") (pintype "passive"))
      (node (ref "U1") (pin "P64") (pinfunction "GND6_P64") (pintype "passive"))
      (node (ref "U1") (pin "P67") (pinfunction "GND7_P67") (pintype "passive"))
      (node (ref "U1") (pin "P81") (pinfunction "GND8_P81") (pintype "passive"))
      (node (ref "U1") (pin "P88") (pinfunction "GND9_P88") (pintype "passive"))
      (node (ref "U1") (pin "P9") (pinfunction "GND0_P9") (pintype "passive"))
      (node (ref "U1") (pin "P94") (pinfunction "GND10_P94") (pintype "passive"))
      (node (ref "X1") (pin "3") (pinfunction "2_3") (pintype "passive"))
      (node (ref "X2") (pin "13") (pinfunction "13_13") (pintype "passive"))
      (node (ref "X2") (pin "14") (pinfunction "14_14") (pintype "passive"))
      (node (ref "X2") (pin "17") (pinfunction "17_17") (pintype "passive"))
      (node (ref "X2") (pin "18") (pinfunction "18_18") (pintype "passive"))
      (node (ref "X2") (pin "21") (pinfunction "21_21") (pintype "passive"))
      (node (ref "X2") (pin "4") (pinfunction "4_4") (pintype "passive"))
      (node (ref "X2") (pin "5") (pinfunction "5_5") (pintype "passive"))
      (node (ref "X2") (pin "9") (pinfunction "9_9") (pintype "passive"))
      (node (ref "X3") (pin "3") (pinfunction "3_3") (pintype "passive"))
      (node (ref "X3") (pin "SH2") (pinfunction "PE2_SH2") (pintype "power_in"))
      (node (ref "X4") (pin "8") (pinfunction "F_8") (pintype "passive"))
      (node (ref "X4") (pin "G1") (pinfunction "G1_G1") (pintype "passive"))
      (node (ref "X5") (pin "8") (pinfunction "F_8") (pintype "passive"))
      (node (ref "X5") (pin "G1") (pinfunction "G1_G1") (pintype "passive"))
    )
    (net (code "65") (name "Net-(C1-Pad2)") (class "Default")
      (node (ref "C1") (pin "2") (pinfunction "2_2") (pintype "passive"))
      (node (ref "R23") (pin "2") (pinfunction "2_2") (pintype "passive"))
      (node (ref "R48") (pin "1") (pinfunction "1_1") (pintype "passive"))
    )
    (net (code "66") (name "Net-(C2-Pad1)") (class "Default")
      (node (ref "C2") (pin "1") (pinfunction "1_1") (pintype "passive"))
      (node (ref "R17") (pin "2") (pinfunction "2_2") (pintype "passive"))
      (node (ref "X1") (pin "1") (pinfunction "1_1") (pintype "passive"))
    )
    (net (code "67") (name "Net-(C3-Pad1)") (class "Default")
      (node (ref "C3") (pin "1") (pinfunction "1_1") (pintype "passive"))
      (node (ref "R48") (pin "2") (pinfunction "2_2") (pintype "passive"))
    )
    (net (code "68") (name "Net-(C4-Pad1)") (class "Default")
      (node (ref "C4") (pin "1") (pinfunction "1_1") (pintype "passive"))
      (node (ref "R49") (pin "2") (pinfunction "2_2") (pintype "passive"))
    )
    (net (code "69") (name "Net-(C5-Pad2)") (class "Default")
      (node (ref "C5") (pin "2") (pinfunction "2_2") (pintype "passive"))
      (node (ref "R34") (pin "2") (pinfunction "2_2") (pintype "passive"))
      (node (ref "R49") (pin "1") (pinfunction "1_1") (pintype "passive"))
    )
    (net (code "70") (name "Net-(IC1-CLK)") (class "Default")
      (node (ref "IC1") (pin "3") (pinfunction "CLK_3") (pintype "bidirectional"))
      (node (ref "U1") (pin "P72") (pinfunction "CCLK_P72") (pintype "bidirectional"))
    )
    (net (code "71") (name "Net-(IC1-TDI)") (class "Default")
      (node (ref "IC1") (pin "4") (pinfunction "TDI_4") (pintype "bidirectional"))
      (node (ref "U1") (pin "P109") (pinfunction "TDO_P109") (pintype "bidirectional"))
    )
    (net (code "72") (name "Net-(IC1-{slash}CE)") (class "Default")
      (node (ref "IC1") (pin "10") (pinfunction "/CE_10") (pintype "bidirectional"))
      (node (ref "U1") (pin "P71") (pinfunction "DONE_P71") (pintype "bidirectional"))
    )
    (net (code "73") (name "Net-(IC1-{slash}CF)") (class "Default")
      (node (ref "IC1") (pin "7") (pinfunction "/CF_7") (pintype "bidirectional"))
      (node (ref "U1") (pin "P143") (pinfunction "PROG_B_P143") (pintype "bidirectional"))
    )
    (net (code "74") (name "Net-(Q5-B)") (class "Default")
      (node (ref "Q5") (pin "1") (pinfunction "B_1") (pintype "passive"))
      (node (ref "R8") (pin "2") (pinfunction "2_2") (pintype "passive"))
    )
    (net (code "75") (name "Net-(Q5-E)") (class "Default")
      (node (ref "Q5") (pin "2") (pinfunction "E_2") (pintype "passive"))
      (node (ref "R13") (pin "2") (pinfunction "2_2") (pintype "passive"))
      (node (ref "R14") (pin "2") (pinfunction "2_2") (pintype "passive"))
    )
    (net (code "76") (name "Net-(Q6-B)") (class "Default")
      (node (ref "Q6") (pin "1") (pinfunction "B_1") (pintype "passive"))
      (node (ref "R10") (pin "2") (pinfunction "2_2") (pintype "passive"))
      (node (ref "R9") (pin "2") (pinfunction "2_2") (pintype "passive"))
    )
    (net (code "77") (name "Net-(Q6-E)") (class "Default")
      (node (ref "Q6") (pin "2") (pinfunction "E_2") (pintype "passive"))
      (node (ref "R15") (pin "2") (pinfunction "2_2") (pintype "passive"))
      (node (ref "R16") (pin "2") (pinfunction "2_2") (pintype "passive"))
      (node (ref "R20") (pin "2") (pinfunction "2_2") (pintype "passive"))
    )
    (net (code "78") (name "Net-(Q7-B)") (class "Default")
      (node (ref "Q7") (pin "1") (pinfunction "B_1") (pintype "passive"))
      (node (ref "R29") (pin "2") (pinfunction "2_2") (pintype "passive"))
      (node (ref "R30") (pin "2") (pinfunction "2_2") (pintype "passive"))
    )
    (net (code "79") (name "Net-(Q7-E)") (class "Default")
      (node (ref "Q7") (pin "2") (pinfunction "E_2") (pintype "passive"))
      (node (ref "R31") (pin "2") (pinfunction "2_2") (pintype "passive"))
      (node (ref "R32") (pin "2") (pinfunction "2_2") (pintype "passive"))
      (node (ref "R33") (pin "2") (pinfunction "2_2") (pintype "passive"))
    )
    (net (code "80") (name "Net-(Q8-B)") (class "Default")
      (node (ref "Q8") (pin "1") (pinfunction "B_1") (pintype "passive"))
      (node (ref "R24") (pin "2") (pinfunction "2_2") (pintype "passive"))
      (node (ref "R25") (pin "2") (pinfunction "2_2") (pintype "passive"))
    )
    (net (code "81") (name "Net-(Q8-E)") (class "Default")
      (node (ref "Q8") (pin "2") (pinfunction "E_2") (pintype "passive"))
      (node (ref "R26") (pin "2") (pinfunction "2_2") (pintype "passive"))
      (node (ref "R27") (pin "2") (pinfunction "2_2") (pintype "passive"))
      (node (ref "R28") (pin "2") (pinfunction "2_2") (pintype "passive"))
    )
    (net (code "82") (name "Net-(R18-Pad2)") (class "Default")
      (node (ref "R18") (pin "2") (pinfunction "2_2") (pintype "passive"))
      (node (ref "R22") (pin "2") (pinfunction "2_2") (pintype "passive"))
    )
    (net (code "83") (name "Net-(T2-B)") (class "Default")
      (node (ref "C2") (pin "2") (pinfunction "2_2") (pintype "passive"))
      (node (ref "R18") (pin "1") (pinfunction "1_1") (pintype "passive"))
      (node (ref "R19") (pin "2") (pinfunction "2_2") (pintype "passive"))
      (node (ref "T2") (pin "1") (pinfunction "B_1") (pintype "passive"))
    )
    (net (code "84") (name "Net-(U$1-A0)") (class "Default")
      (node (ref "U$1") (pin "P20") (pinfunction "A0_P20") (pintype "bidirectional"))
      (node (ref "U1") (pin "P77") (pinfunction "IO_L20P_3_P77") (pintype "bidirectional"))
    )
    (net (code "85") (name "Net-(U$1-A1)") (class "Default")
      (node (ref "U$1") (pin "P19") (pinfunction "A1_P19") (pintype "bidirectional"))
      (node (ref "U1") (pin "P76") (pinfunction "IO_P76") (pintype "bidirectional"))
    )
    (net (code "86") (name "Net-(U$1-A2)") (class "Default")
      (node (ref "U$1") (pin "P18") (pinfunction "A2_P18") (pintype "bidirectional"))
      (node (ref "U1") (pin "P74") (pinfunction "IO_L01N_3VRP_3_P74") (pintype "bidirectional"))
    )
    (net (code "87") (name "Net-(U$1-A3)") (class "Default")
      (node (ref "U$1") (pin "P17") (pinfunction "A3_P17") (pintype "bidirectional"))
      (node (ref "U1") (pin "P73") (pinfunction "IO_L01P_3VRN_3_P73") (pintype "bidirectional"))
    )
    (net (code "88") (name "Net-(U$1-A4)") (class "Default")
      (node (ref "U$1") (pin "P16") (pinfunction "A4_P16") (pintype "bidirectional"))
      (node (ref "U1") (pin "P108") (pinfunction "IO_L01N_2VRP_2_P108") (pintype "bidirectional"))
    )
    (net (code "89") (name "Net-(U$1-A5)") (class "Default")
      (node (ref "U$1") (pin "P15") (pinfunction "A5_P15") (pintype "bidirectional"))
      (node (ref "U1") (pin "P107") (pinfunction "IO_L01P_2VRN_2_P107") (pintype "bidirectional"))
    )
    (net (code "90") (name "Net-(U$1-A6)") (class "Default")
      (node (ref "U$1") (pin "P14") (pinfunction "A6_P14") (pintype "bidirectional"))
      (node (ref "U1") (pin "P105") (pinfunction "IO_L20N_2_P105") (pintype "bidirectional"))
    )
    (net (code "91") (name "Net-(U$1-A7)") (class "Default")
      (node (ref "U$1") (pin "P13") (pinfunction "A7_P13") (pintype "bidirectional"))
      (node (ref "U1") (pin "P104") (pinfunction "IO_L20P_2_P104") (pintype "bidirectional"))
    )
    (net (code "92") (name "Net-(U$1-A8)") (class "Default")
      (node (ref "U$1") (pin "P3") (pinfunction "A8_P3") (pintype "bidirectional"))
      (node (ref "U1") (pin "P93") (pinfunction "IO_L40N_2_P93") (pintype "bidirectional"))
    )
    (net (code "93") (name "Net-(U$1-A9)") (class "Default")
      (node (ref "U$1") (pin "P2") (pinfunction "A9_P2") (pintype "bidirectional"))
      (node (ref "U1") (pin "P92") (pinfunction "IO_L40P_2VREF_2_P92") (pintype "bidirectional"))
    )
    (net (code "94") (name "Net-(U$1-A10)") (class "Default")
      (node (ref "U$1") (pin "P31") (pinfunction "A10_P31") (pintype "bidirectional"))
      (node (ref "U1") (pin "P87") (pinfunction "IO_L24N_3_P87") (pintype "bidirectional"))
    )
    (net (code "95") (name "Net-(U$1-A11)") (class "Default")
      (node (ref "U$1") (pin "P1") (pinfunction "A11_P1") (pintype "bidirectional"))
      (node (ref "U1") (pin "P90") (pinfunction "IO_L40N_3VREF_3_P90") (pintype "bidirectional"))
    )
    (net (code "96") (name "Net-(U$1-A12)") (class "Default")
      (node (ref "U$1") (pin "P12") (pinfunction "A12_P12") (pintype "bidirectional"))
      (node (ref "U1") (pin "P103") (pinfunction "IO_L21N_2_P103") (pintype "bidirectional"))
    )
    (net (code "97") (name "Net-(U$1-A13)") (class "Default")
      (node (ref "U$1") (pin "P4") (pinfunction "A13_P4") (pintype "bidirectional"))
      (node (ref "U1") (pin "P95") (pinfunction "IO_L24P_2_P95") (pintype "bidirectional"))
    )
    (net (code "98") (name "Net-(U$1-A14)") (class "Default")
      (node (ref "U$1") (pin "P11") (pinfunction "A14_P11") (pintype "bidirectional"))
      (node (ref "U1") (pin "P102") (pinfunction "IO_L21P_2_P102") (pintype "bidirectional"))
    )
    (net (code "99") (name "Net-(U$1-A15)") (class "Default")
      (node (ref "U$1") (pin "P7") (pinfunction "A15_P7") (pintype "bidirectional"))
      (node (ref "U1") (pin "P98") (pinfunction "IO_L23N_2VREF_2_P98") (pintype "bidirectional"))
    )
    (net (code "100") (name "Net-(U$1-A16)") (class "Default")
      (node (ref "U$1") (pin "P10") (pinfunction "A16_P10") (pintype "bidirectional"))
      (node (ref "U1") (pin "P100") (pinfunction "IO_L22N_2_P100") (pintype "bidirectional"))
    )
    (net (code "101") (name "Net-(U$1-A17)") (class "Default")
      (node (ref "U$1") (pin "P6") (pinfunction "A17_P6") (pintype "bidirectional"))
      (node (ref "U1") (pin "P97") (pinfunction "IO_L23P_2_P97") (pintype "bidirectional"))
    )
    (net (code "102") (name "Net-(U$1-A18)") (class "Default")
      (node (ref "U$1") (pin "P9") (pinfunction "A18_P9") (pintype "bidirectional"))
      (node (ref "U1") (pin "P99") (pinfunction "IO_L22P_2_P99") (pintype "bidirectional"))
    )
    (net (code "103") (name "Net-(U$1-DQ0)") (class "Default")
      (node (ref "U$1") (pin "P21") (pinfunction "DQ0_P21") (pintype "bidirectional"))
      (node (ref "U1") (pin "P78") (pinfunction "IO_L20N_3_P78") (pintype "bidirectional"))
    )
    (net (code "104") (name "Net-(U$1-DQ1)") (class "Default")
      (node (ref "U$1") (pin "P22") (pinfunction "DQ1_P22") (pintype "bidirectional"))
      (node (ref "U1") (pin "P79") (pinfunction "IO_L21P_3_P79") (pintype "bidirectional"))
    )
    (net (code "105") (name "Net-(U$1-DQ2)") (class "Default")
      (node (ref "U$1") (pin "P23") (pinfunction "DQ2_P23") (pintype "bidirectional"))
      (node (ref "U1") (pin "P80") (pinfunction "IO_L21N_3_P80") (pintype "bidirectional"))
    )
    (net (code "106") (name "Net-(U$1-DQ3)") (class "Default")
      (node (ref "U$1") (pin "P25") (pinfunction "DQ3_P25") (pintype "bidirectional"))
      (node (ref "U1") (pin "P82") (pinfunction "IO_L22P_3_P82") (pintype "bidirectional"))
    )
    (net (code "107") (name "Net-(U$1-DQ4)") (class "Default")
      (node (ref "U$1") (pin "P26") (pinfunction "DQ4_P26") (pintype "bidirectional"))
      (node (ref "U1") (pin "P83") (pinfunction "IO_L22N_3_P83") (pintype "bidirectional"))
    )
    (net (code "108") (name "Net-(U$1-DQ5)") (class "Default")
      (node (ref "U$1") (pin "P27") (pinfunction "DQ5_P27") (pintype "bidirectional"))
      (node (ref "U1") (pin "P84") (pinfunction "IO_L23P_3VREF_3_P84") (pintype "bidirectional"))
    )
    (net (code "109") (name "Net-(U$1-DQ6)") (class "Default")
      (node (ref "U$1") (pin "P28") (pinfunction "DQ6_P28") (pintype "bidirectional"))
      (node (ref "U1") (pin "P85") (pinfunction "IO_L23N_3_P85") (pintype "bidirectional"))
    )
    (net (code "110") (name "Net-(U$1-DQ7)") (class "Default")
      (node (ref "U$1") (pin "P29") (pinfunction "DQ7_P29") (pintype "bidirectional"))
      (node (ref "U1") (pin "P86") (pinfunction "IO_L24P_3_P86") (pintype "bidirectional"))
    )
    (net (code "111") (name "Net-(U$1-OE)") (class "Default")
      (node (ref "U$1") (pin "P32") (pinfunction "OE_P32") (pintype "bidirectional"))
      (node (ref "U1") (pin "P89") (pinfunction "IO_L40P_3_P89") (pintype "bidirectional"))
    )
    (net (code "112") (name "Net-(U$1-WE)") (class "Default")
      (node (ref "U$1") (pin "P5") (pinfunction "WE_P5") (pintype "bidirectional"))
      (node (ref "U1") (pin "P96") (pinfunction "IO_L24N_2_P96") (pintype "bidirectional"))
    )
    (net (code "113") (name "Net-(U1N-TCK)") (class "Default")
      (node (ref "R2") (pin "1") (pinfunction "1_1") (pintype "passive"))
      (node (ref "U1") (pin "P110") (pinfunction "TCK_P110") (pintype "bidirectional"))
    )
    (net (code "114") (name "Net-(U1N-TDI)") (class "Default")
      (node (ref "R1") (pin "1") (pinfunction "1_1") (pintype "passive"))
      (node (ref "U1") (pin "P144") (pinfunction "TDI_P144") (pintype "bidirectional"))
    )
    (net (code "115") (name "Net-(U1N-TMS)") (class "Default")
      (node (ref "R3") (pin "1") (pinfunction "1_1") (pintype "passive"))
      (node (ref "U1") (pin "P111") (pinfunction "TMS_P111") (pintype "bidirectional"))
    )
    (net (code "116") (name "Net-(X4A-F)") (class "Default")
      (node (ref "R40") (pin "2") (pinfunction "2_2") (pintype "passive"))
      (node (ref "X4") (pin "1") (pinfunction "F_1") (pintype "passive"))
    )
    (net (code "117") (name "Net-(X4B-F)") (class "Default")
      (node (ref "R41") (pin "2") (pinfunction "2_2") (pintype "passive"))
      (node (ref "X4") (pin "2") (pinfunction "F_2") (pintype "passive"))
    )
    (net (code "118") (name "Net-(X4C-F)") (class "Default")
      (node (ref "R42") (pin "2") (pinfunction "2_2") (pintype "passive"))
      (node (ref "X4") (pin "3") (pinfunction "F_3") (pintype "passive"))
    )
    (net (code "119") (name "Net-(X4D-F)") (class "Default")
      (node (ref "R43") (pin "2") (pinfunction "2_2") (pintype "passive"))
      (node (ref "X4") (pin "4") (pinfunction "F_4") (pintype "passive"))
    )
    (net (code "120") (name "Net-(X4F-F)") (class "Default")
      (node (ref "R44") (pin "2") (pinfunction "2_2") (pintype "passive"))
      (node (ref "X4") (pin "6") (pinfunction "F_6") (pintype "passive"))
    )
    (net (code "121") (name "Net-(X4G-F)") (class "Default")
      (node (ref "R45") (pin "2") (pinfunction "2_2") (pintype "passive"))
      (node (ref "X4") (pin "7") (pinfunction "F_7") (pintype "passive"))
    )
    (net (code "122") (name "Net-(X5A-F)") (class "Default")
      (node (ref "R46") (pin "1") (pinfunction "1_1") (pintype "passive"))
      (node (ref "X5") (pin "1") (pinfunction "F_1") (pintype "passive"))
    )
    (net (code "123") (name "Net-(X5B-F)") (class "Default")
      (node (ref "R39") (pin "1") (pinfunction "1_1") (pintype "passive"))
      (node (ref "X5") (pin "2") (pinfunction "F_2") (pintype "passive"))
    )
    (net (code "124") (name "Net-(X5C-F)") (class "Default")
      (node (ref "R38") (pin "1") (pinfunction "1_1") (pintype "passive"))
      (node (ref "X5") (pin "3") (pinfunction "F_3") (pintype "passive"))
    )
    (net (code "125") (name "Net-(X5D-F)") (class "Default")
      (node (ref "R37") (pin "1") (pinfunction "1_1") (pintype "passive"))
      (node (ref "X5") (pin "4") (pinfunction "F_4") (pintype "passive"))
    )
    (net (code "126") (name "Net-(X5F-F)") (class "Default")
      (node (ref "R36") (pin "1") (pinfunction "1_1") (pintype "passive"))
      (node (ref "X5") (pin "6") (pinfunction "F_6") (pintype "passive"))
    )
    (net (code "127") (name "Net-(X5G-F)") (class "Default")
      (node (ref "R35") (pin "1") (pinfunction "1_1") (pintype "passive"))
      (node (ref "X5") (pin "7") (pinfunction "F_7") (pintype "passive"))
    )
    (net (code "128") (name "unconnected-(IC1-NC.1-Pad2)") (class "Default")
      (node (ref "IC1") (pin "2") (pinfunction "NC.1_2") (pintype "bidirectional"))
    )
    (net (code "129") (name "unconnected-(IC1-NC.2-Pad9)") (class "Default")
      (node (ref "IC1") (pin "9") (pinfunction "NC.2_9") (pintype "bidirectional"))
    )
    (net (code "130") (name "unconnected-(IC1-NC.3-Pad12)") (class "Default")
      (node (ref "IC1") (pin "12") (pinfunction "NC.3_12") (pintype "bidirectional"))
    )
    (net (code "131") (name "unconnected-(IC1-NC.4-Pad14)") (class "Default")
      (node (ref "IC1") (pin "14") (pinfunction "NC.4_14") (pintype "bidirectional"))
    )
    (net (code "132") (name "unconnected-(IC1-NC.5-Pad15)") (class "Default")
      (node (ref "IC1") (pin "15") (pinfunction "NC.5_15") (pintype "bidirectional"))
    )
    (net (code "133") (name "unconnected-(IC1-NC.6-Pad16)") (class "Default")
      (node (ref "IC1") (pin "16") (pinfunction "NC.6_16") (pintype "bidirectional"))
    )
    (net (code "134") (name "unconnected-(IC1-{slash}CEO-Pad13)") (class "Default")
      (node (ref "IC1") (pin "13") (pinfunction "/CEO_13") (pintype "bidirectional"))
    )
    (net (code "135") (name "unconnected-(IC3-AVCC-Pad32)") (class "Default")
      (node (ref "IC3") (pin "32") (pinfunction "AVCC_32") (pintype "bidirectional"))
    )
    (net (code "136") (name "unconnected-(IC3-D+-Pad29)") (class "Default")
      (node (ref "IC3") (pin "29") (pinfunction "D+_29") (pintype "bidirectional"))
    )
    (net (code "137") (name "unconnected-(IC3-D--Pad30)") (class "Default")
      (node (ref "IC3") (pin "30") (pinfunction "D-_30") (pintype "bidirectional"))
    )
    (net (code "138") (name "unconnected-(IC3-GND-Pad3)") (class "Default")
      (node (ref "IC3") (pin "3") (pinfunction "GND_3") (pintype "bidirectional"))
    )
    (net (code "139") (name "unconnected-(IC3-PC2(AIN2{slash}PCIN11)-Pad5)") (class "Default")
      (node (ref "IC3") (pin "5") (pinfunction "PC2(AIN2/PCIN11)_5") (pintype "bidirectional"))
    )
    (net (code "140") (name "unconnected-(IC3-PC4(PCINT10)-Pad26)") (class "Default")
      (node (ref "IC3") (pin "26") (pinfunction "PC4(PCINT10)_26") (pintype "bidirectional"))
    )
    (net (code "141") (name "unconnected-(IC3-PC5(OC1B{slash}PCINT9)-Pad25)") (class "Default")
      (node (ref "IC3") (pin "25") (pinfunction "PC5(OC1B/PCINT9)_25") (pintype "bidirectional"))
    )
    (net (code "142") (name "unconnected-(IC3-PC6(OC1A{slash}PCINT8)-Pad23)") (class "Default")
      (node (ref "IC3") (pin "23") (pinfunction "PC6(OC1A/PCINT8)_23") (pintype "bidirectional"))
    )
    (net (code "143") (name "unconnected-(IC3-PD0(INT0{slash}OC0B)-Pad6)") (class "Default")
      (node (ref "IC3") (pin "6") (pinfunction "PD0(INT0/OC0B)_6") (pintype "bidirectional"))
    )
    (net (code "144") (name "unconnected-(IC3-PD1(INT1{slash}AIN0)-Pad7)") (class "Default")
      (node (ref "IC3") (pin "7") (pinfunction "PD1(INT1/AIN0)_7") (pintype "bidirectional"))
    )
    (net (code "145") (name "unconnected-(IC3-PD4(INT5{slash}AIN3)-Pad10)") (class "Default")
      (node (ref "IC3") (pin "10") (pinfunction "PD4(INT5/AIN3)_10") (pintype "bidirectional"))
    )
    (net (code "146") (name "unconnected-(IC3-PD5(XCK{slash}AIN4{slash}PCINT12)-Pad11)") (class "Default")
      (node (ref "IC3") (pin "11") (pinfunction "PD5(XCK/AIN4/PCINT12)_11") (pintype "bidirectional"))
    )
    (net (code "147") (name "unconnected-(IC3-PD6(INT6{slash}AIN5{slash}RTS)-Pad12)") (class "Default")
      (node (ref "IC3") (pin "12") (pinfunction "PD6(INT6/AIN5/RTS)_12") (pintype "bidirectional"))
    )
    (net (code "148") (name "unconnected-(IC3-UCAP-Pad27)") (class "Default")
      (node (ref "IC3") (pin "27") (pinfunction "UCAP_27") (pintype "bidirectional"))
    )
    (net (code "149") (name "unconnected-(IC3-UGND-Pad28)") (class "Default")
      (node (ref "IC3") (pin "28") (pinfunction "UGND_28") (pintype "bidirectional"))
    )
    (net (code "150") (name "unconnected-(IC3-UVCC-Pad31)") (class "Default")
      (node (ref "IC3") (pin "31") (pinfunction "UVCC_31") (pintype "bidirectional"))
    )
    (net (code "151") (name "unconnected-(IC3-VCC-Pad4)") (class "Default")
      (node (ref "IC3") (pin "4") (pinfunction "VCC_4") (pintype "bidirectional"))
    )
    (net (code "152") (name "unconnected-(IC3-XTAL1-Pad1)") (class "Default")
      (node (ref "IC3") (pin "1") (pinfunction "XTAL1_1") (pintype "bidirectional"))
    )
    (net (code "153") (name "unconnected-(IC3-XTAL2{slash}PC0-Pad2)") (class "Default")
      (node (ref "IC3") (pin "2") (pinfunction "XTAL2/PC0_2") (pintype "bidirectional"))
    )
    (net (code "154") (name "unconnected-(IC3-{slash}RESET(PC1)-Pad24)") (class "Default")
      (node (ref "IC3") (pin "24") (pinfunction "/RESET(PC1)_24") (pintype "bidirectional"))
    )
    (net (code "155") (name "unconnected-(REG1.2-VOUT2-Pad2)") (class "Default")
      (node (ref "REG1.2") (pin "2") (pinfunction "VOUT2_2") (pintype "bidirectional"))
    )
    (net (code "156") (name "unconnected-(U$2-TRI-PadENA)") (class "Default")
      (node (ref "U$2") (pin "ENA") (pinfunction "TRI_ENA") (pintype "input"))
    )
    (net (code "157") (name "unconnected-(U1A-IO_L27P_0-PadP135)") (class "Default")
      (node (ref "U1") (pin "P135") (pinfunction "IO_L27P_0_P135") (pintype "bidirectional"))
    )
    (net (code "158") (name "unconnected-(U1A-IO_L30N_0-PadP132)") (class "Default")
      (node (ref "U1") (pin "P132") (pinfunction "IO_L30N_0_P132") (pintype "bidirectional"))
    )
    (net (code "159") (name "unconnected-(U1A-IO_L30P_0-PadP131)") (class "Default")
      (node (ref "U1") (pin "P131") (pinfunction "IO_L30P_0_P131") (pintype "bidirectional"))
    )
    (net (code "160") (name "unconnected-(U1A-IO_L31N_0-PadP130)") (class "Default")
      (node (ref "U1") (pin "P130") (pinfunction "IO_L31N_0_P130") (pintype "bidirectional"))
    )
    (net (code "161") (name "unconnected-(U1A-IO_L31P_0VREF_0-PadP129)") (class "Default")
      (node (ref "U1") (pin "P129") (pinfunction "IO_L31P_0VREF_0_P129") (pintype "bidirectional"))
    )
    (net (code "162") (name "unconnected-(U1A-IO_L32N_0GCLK7-PadP128)") (class "Default")
      (node (ref "U1") (pin "P128") (pinfunction "IO_L32N_0GCLK7_P128") (pintype "bidirectional"))
    )
    (net (code "163") (name "unconnected-(U1A-IO_L32P_0GCLK6-PadP127)") (class "Default")
      (node (ref "U1") (pin "P127") (pinfunction "IO_L32P_0GCLK6_P127") (pintype "bidirectional"))
    )
    (net (code "164") (name "unconnected-(U1C-IO-PadP116)") (class "Default")
      (node (ref "U1") (pin "P116") (pinfunction "IO_P116") (pintype "bidirectional"))
    )
    (net (code "165") (name "unconnected-(U1C-IO_L01N_1VRP_1-PadP113)") (class "Default")
      (node (ref "U1") (pin "P113") (pinfunction "IO_L01N_1VRP_1_P113") (pintype "bidirectional"))
    )
    (net (code "166") (name "unconnected-(U1C-IO_L01P_1VRN_1-PadP112)") (class "Default")
      (node (ref "U1") (pin "P112") (pinfunction "IO_L01P_1VRN_1_P112") (pintype "bidirectional"))
    )
    (net (code "167") (name "unconnected-(U1C-IO_L28N_1-PadP119)") (class "Default")
      (node (ref "U1") (pin "P119") (pinfunction "IO_L28N_1_P119") (pintype "bidirectional"))
    )
    (net (code "168") (name "unconnected-(U1C-IO_L28P_1-PadP118)") (class "Default")
      (node (ref "U1") (pin "P118") (pinfunction "IO_L28P_1_P118") (pintype "bidirectional"))
    )
    (net (code "169") (name "unconnected-(U1C-IO_L31N_1VREF_1-PadP123)") (class "Default")
      (node (ref "U1") (pin "P123") (pinfunction "IO_L31N_1VREF_1_P123") (pintype "bidirectional"))
    )
    (net (code "170") (name "unconnected-(U1C-IO_L31P_1-PadP122)") (class "Default")
      (node (ref "U1") (pin "P122") (pinfunction "IO_L31P_1_P122") (pintype "bidirectional"))
    )
    (net (code "171") (name "unconnected-(U1C-IO_L32N_1GCLK5-PadP125)") (class "Default")
      (node (ref "U1") (pin "P125") (pinfunction "IO_L32N_1GCLK5_P125") (pintype "bidirectional"))
    )
    (net (code "172") (name "unconnected-(U1C-IO_L32P_1GCLK4-PadP124)") (class "Default")
      (node (ref "U1") (pin "P124") (pinfunction "IO_L32P_1GCLK4_P124") (pintype "bidirectional"))
    )
    (net (code "173") (name "unconnected-(U1J-IO_L01N_6VRP_6-PadP36)") (class "Default")
      (node (ref "U1") (pin "P36") (pinfunction "IO_L01N_6VRP_6_P36") (pintype "bidirectional"))
    )
    (net (code "174") (name "unconnected-(U1J-IO_L01P_6VRN_6-PadP35)") (class "Default")
      (node (ref "U1") (pin "P35") (pinfunction "IO_L01P_6VRN_6_P35") (pintype "bidirectional"))
    )
    (net (code "175") (name "unconnected-(U1J-IO_L20N_6-PadP33)") (class "Default")
      (node (ref "U1") (pin "P33") (pinfunction "IO_L20N_6_P33") (pintype "bidirectional"))
    )
    (net (code "176") (name "unconnected-(U1J-IO_L20P_6-PadP32)") (class "Default")
      (node (ref "U1") (pin "P32") (pinfunction "IO_L20P_6_P32") (pintype "bidirectional"))
    )
    (net (code "177") (name "unconnected-(U1J-IO_L21N_6-PadP31)") (class "Default")
      (node (ref "U1") (pin "P31") (pinfunction "IO_L21N_6_P31") (pintype "bidirectional"))
    )
    (net (code "178") (name "unconnected-(U1J-IO_L21P_6-PadP30)") (class "Default")
      (node (ref "U1") (pin "P30") (pinfunction "IO_L21P_6_P30") (pintype "bidirectional"))
    )
    (net (code "179") (name "unconnected-(U1J-IO_L22N_6-PadP28)") (class "Default")
      (node (ref "U1") (pin "P28") (pinfunction "IO_L22N_6_P28") (pintype "bidirectional"))
    )
    (net (code "180") (name "unconnected-(U1J-IO_L22P_6-PadP27)") (class "Default")
      (node (ref "U1") (pin "P27") (pinfunction "IO_L22P_6_P27") (pintype "bidirectional"))
    )
    (net (code "181") (name "unconnected-(U1J-IO_L23N_6-PadP26)") (class "Default")
      (node (ref "U1") (pin "P26") (pinfunction "IO_L23N_6_P26") (pintype "bidirectional"))
    )
    (net (code "182") (name "unconnected-(U1J-IO_L23P_6-PadP25)") (class "Default")
      (node (ref "U1") (pin "P25") (pinfunction "IO_L23P_6_P25") (pintype "bidirectional"))
    )
    (net (code "183") (name "unconnected-(U1J-IO_L24N_6VREF_6-PadP24)") (class "Default")
      (node (ref "U1") (pin "P24") (pinfunction "IO_L24N_6VREF_6_P24") (pintype "bidirectional"))
    )
    (net (code "184") (name "unconnected-(U1J-IO_L24P_6-PadP23)") (class "Default")
      (node (ref "U1") (pin "P23") (pinfunction "IO_L24P_6_P23") (pintype "bidirectional"))
    )
    (net (code "185") (name "unconnected-(U1J-IO_L40N_6-PadP21)") (class "Default")
      (node (ref "U1") (pin "P21") (pinfunction "IO_L40N_6_P21") (pintype "bidirectional"))
    )
    (net (code "186") (name "unconnected-(U1J-IO_L40P_6VREF_6-PadP20)") (class "Default")
      (node (ref "U1") (pin "P20") (pinfunction "IO_L40P_6VREF_6_P20") (pintype "bidirectional"))
    )
    (net (code "187") (name "unconnected-(U1L-IOVREF_7-PadP4)") (class "Default")
      (node (ref "U1") (pin "P4") (pinfunction "IOVREF_7_P4") (pintype "bidirectional"))
    )
    (net (code "188") (name "unconnected-(U1L-IO_L01N_7VRP_7-PadP2)") (class "Default")
      (node (ref "U1") (pin "P2") (pinfunction "IO_L01N_7VRP_7_P2") (pintype "bidirectional"))
    )
    (net (code "189") (name "unconnected-(U1L-IO_L01P_7VRN_7-PadP1)") (class "Default")
      (node (ref "U1") (pin "P1") (pinfunction "IO_L01P_7VRN_7_P1") (pintype "bidirectional"))
    )
    (net (code "190") (name "unconnected-(U1L-IO_L20N_7-PadP6)") (class "Default")
      (node (ref "U1") (pin "P6") (pinfunction "IO_L20N_7_P6") (pintype "bidirectional"))
    )
    (net (code "191") (name "unconnected-(U1L-IO_L20P_7-PadP5)") (class "Default")
      (node (ref "U1") (pin "P5") (pinfunction "IO_L20P_7_P5") (pintype "bidirectional"))
    )
    (net (code "192") (name "unconnected-(U1L-IO_L21N_7-PadP8)") (class "Default")
      (node (ref "U1") (pin "P8") (pinfunction "IO_L21N_7_P8") (pintype "bidirectional"))
    )
    (net (code "193") (name "unconnected-(U1L-IO_L21P_7-PadP7)") (class "Default")
      (node (ref "U1") (pin "P7") (pinfunction "IO_L21P_7_P7") (pintype "bidirectional"))
    )
    (net (code "194") (name "unconnected-(U1L-IO_L22N_7-PadP11)") (class "Default")
      (node (ref "U1") (pin "P11") (pinfunction "IO_L22N_7_P11") (pintype "bidirectional"))
    )
    (net (code "195") (name "unconnected-(U1L-IO_L22P_7-PadP10)") (class "Default")
      (node (ref "U1") (pin "P10") (pinfunction "IO_L22P_7_P10") (pintype "bidirectional"))
    )
    (net (code "196") (name "unconnected-(U1L-IO_L23N_7-PadP13)") (class "Default")
      (node (ref "U1") (pin "P13") (pinfunction "IO_L23N_7_P13") (pintype "bidirectional"))
    )
    (net (code "197") (name "unconnected-(U1L-IO_L23P_7-PadP12)") (class "Default")
      (node (ref "U1") (pin "P12") (pinfunction "IO_L23P_7_P12") (pintype "bidirectional"))
    )
    (net (code "198") (name "unconnected-(U1L-IO_L24N_7-PadP15)") (class "Default")
      (node (ref "U1") (pin "P15") (pinfunction "IO_L24N_7_P15") (pintype "bidirectional"))
    )
    (net (code "199") (name "unconnected-(U1L-IO_L24P_7-PadP14)") (class "Default")
      (node (ref "U1") (pin "P14") (pinfunction "IO_L24P_7_P14") (pintype "bidirectional"))
    )
    (net (code "200") (name "unconnected-(U1L-IO_L40N_7VREF_7-PadP18)") (class "Default")
      (node (ref "U1") (pin "P18") (pinfunction "IO_L40N_7VREF_7_P18") (pintype "bidirectional"))
    )
    (net (code "201") (name "unconnected-(U1L-IO_L40P_7-PadP17)") (class "Default")
      (node (ref "U1") (pin "P17") (pinfunction "IO_L40P_7_P17") (pintype "bidirectional"))
    )
    (net (code "202") (name "unconnected-(U1N-HSWAP_EN-PadP142)") (class "Default")
      (node (ref "U1") (pin "P142") (pinfunction "HSWAP_EN_P142") (pintype "bidirectional"))
    )
    (net (code "203") (name "unconnected-(X1-3-Pad2)") (class "Default")
      (node (ref "X1") (pin "2") (pinfunction "3_2") (pintype "passive"))
    )
    (net (code "204") (name "unconnected-(X2-Pad10)") (class "Default")
      (node (ref "X2") (pin "10") (pinfunction "10_10") (pintype "passive"))
    )
    (net (code "205") (name "unconnected-(X2-Pad12)") (class "Default")
      (node (ref "X2") (pin "12") (pinfunction "12_12") (pintype "passive"))
    )
    (net (code "206") (name "unconnected-(X3-Pad2)") (class "Default")
      (node (ref "X3") (pin "2") (pinfunction "2_2") (pintype "passive"))
    )
    (net (code "207") (name "unconnected-(X3-Pad8)") (class "Default")
      (node (ref "X3") (pin "8") (pinfunction "8_8") (pintype "passive"))
    )
    (net (code "208") (name "unconnected-(X4-PadG2)") (class "Default")
      (node (ref "X4") (pin "G2") (pinfunction "G2_G2") (pintype "passive"))
    )
    (net (code "209") (name "unconnected-(X5-PadG2)") (class "Default")
      (node (ref "X5") (pin "G2") (pinfunction "G2_G2") (pintype "passive"))
    )
  )
)
